# STM32.net
KiCad netlist of a schematic drawn in Altium Designer
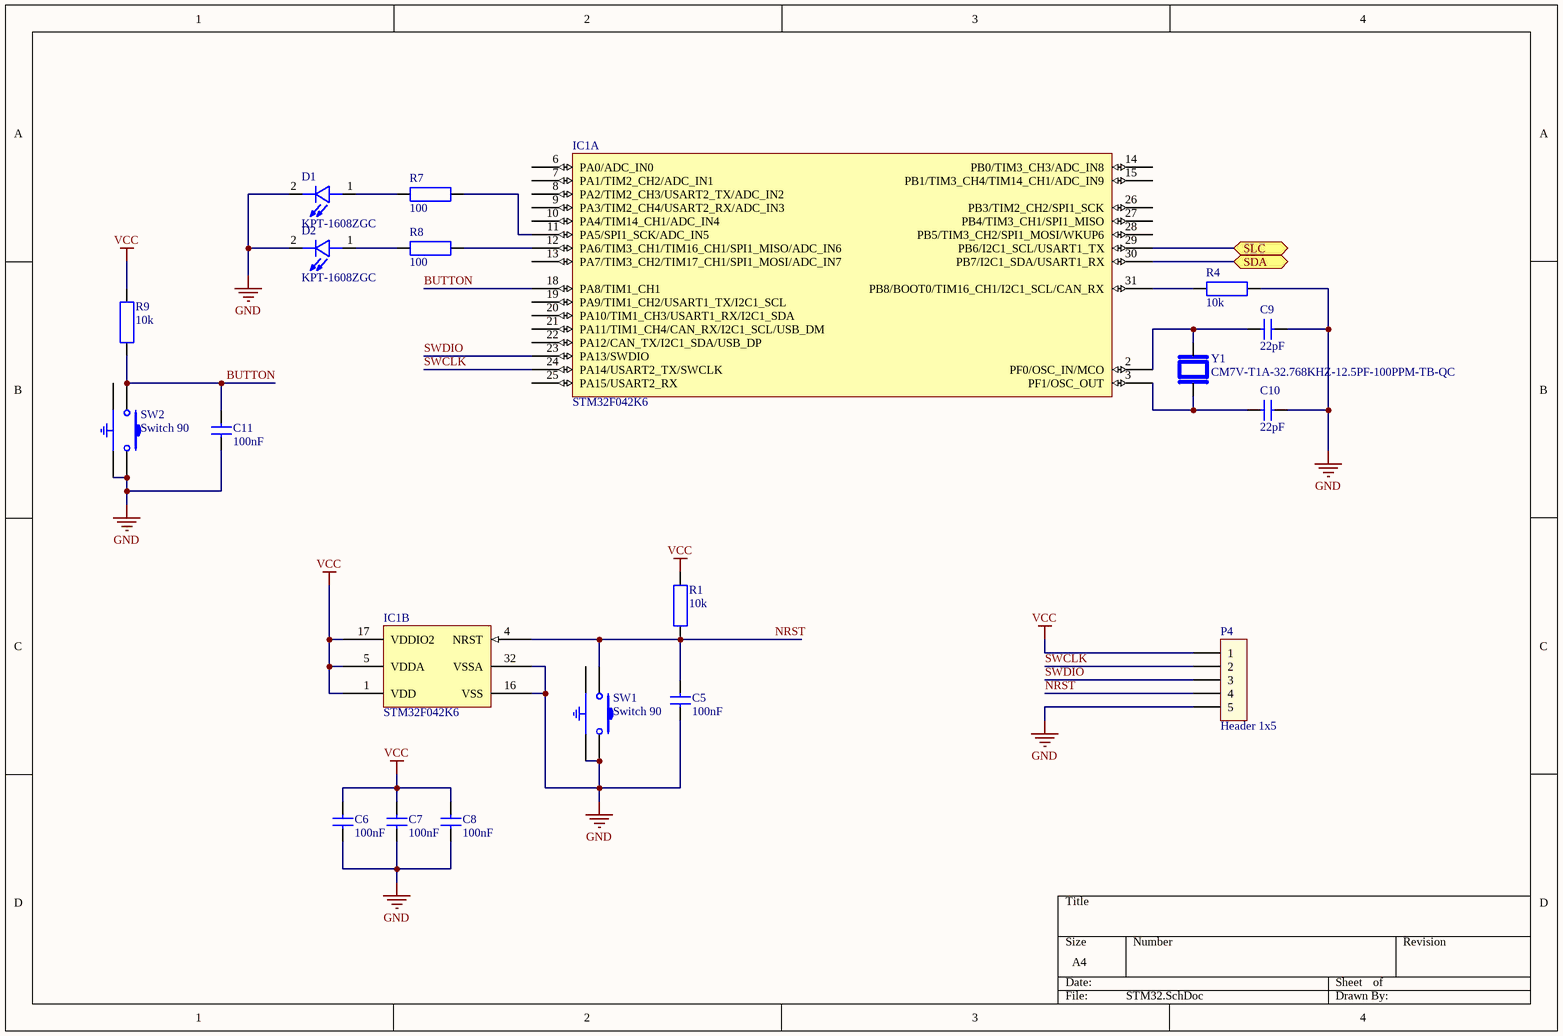
[diagram p0: STM32.SchDoc]

(export (version "E")
  (design (tool "Eeschema 10.0.6"))
  (components
    (comp (ref "C5")
      (value "100nF")
      (footprint "SMD_CAPACITOR_1206")
      (description "Capacitor")
      (libsource (lib "VPP_Library") (part "Capacitor"))
    )
    (comp (ref "C6")
      (value "100nF")
      (footprint "SMD_CAPACITOR_1206")
      (description "Capacitor")
      (libsource (lib "VPP_Library") (part "Capacitor"))
    )
    (comp (ref "C7")
      (value "100nF")
      (footprint "SMD_CAPACITOR_1206")
      (description "Capacitor")
      (libsource (lib "VPP_Library") (part "Capacitor"))
    )
    (comp (ref "C8")
      (value "100nF")
      (footprint "SMD_CAPACITOR_1206")
      (description "Capacitor")
      (libsource (lib "VPP_Library") (part "Capacitor"))
    )
    (comp (ref "C9")
      (value "22pF")
      (footprint "SMD_CAPACITOR_1206")
      (description "Capacitor")
      (libsource (lib "VPP_Library") (part "Capacitor"))
    )
    (comp (ref "C10")
      (value "22pF")
      (footprint "SMD_CAPACITOR_1206")
      (description "Capacitor")
      (libsource (lib "VPP_Library") (part "Capacitor"))
    )
    (comp (ref "C11")
      (value "100nF")
      (footprint "SMD_CAPACITOR_1206")
      (description "Capacitor")
      (libsource (lib "VPP_Library") (part "Capacitor"))
    )
    (comp (ref "D1")
      (value "KPT-1608ZGC")
      (footprint "LED_KPT-1608ZGC")
      (description "1.6x0.8mm Smd Chip Led Lamp")
      (fields (field (name "MF") "Kingbright"))
      (libsource (lib "KPT-1608ZGC") (part "KPT-1608ZGC"))
    )
    (comp (ref "D2")
      (value "KPT-1608ZGC")
      (footprint "LED_KPT-1608ZGC")
      (description "1.6x0.8mm Smd Chip Led Lamp")
      (fields (field (name "MF") "Kingbright"))
      (libsource (lib "KPT-1608ZGC") (part "KPT-1608ZGC"))
    )
    (comp (ref "IC1")
      (value "STM32F042K6")
      (footprint "SMD_LQFP-32")
      (description "ARM Cortex-M0 32-bit MCU, 6 KB Internal RAM, 32 KB Flash, 48 MHz, 32-pin LQFP")
      (libsource (lib "VPP_Library") (part "STM32F042K6"))
    )
    (comp (ref "P4")
      (value "Header 1x5")
      (footprint "THT_HEADER_100MIL_1X5_MALE_90")
      (libsource (lib "VPP_Library") (part "Header_1x5"))
    )
    (comp (ref "R1")
      (value "10k")
      (footprint "SMD_RESISTOR_1206")
      (description "Resistor")
      (libsource (lib "VPP_Library") (part "Resistor"))
    )
    (comp (ref "R4")
      (value "10k")
      (footprint "SMD_RESISTOR_1206")
      (description "Resistor")
      (libsource (lib "VPP_Library") (part "Resistor"))
    )
    (comp (ref "R7")
      (value "100")
      (footprint "SMD_RESISTOR_1206")
      (description "Resistor")
      (libsource (lib "VPP_Library") (part "Resistor"))
    )
    (comp (ref "R8")
      (value "100")
      (footprint "SMD_RESISTOR_1206")
      (description "Resistor")
      (libsource (lib "VPP_Library") (part "Resistor"))
    )
    (comp (ref "R9")
      (value "10k")
      (footprint "SMD_RESISTOR_1206")
      (description "Resistor")
      (libsource (lib "VPP_Library") (part "Resistor"))
    )
    (comp (ref "SW1")
      (value "Switch 90")
      (footprint "SMD_SWITCH_SPST_90")
      (description "Tactile Switch Right Angle")
      (libsource (lib "VPP_Library") (part "Switch_90"))
    )
    (comp (ref "SW2")
      (value "Switch 90")
      (footprint "SMD_SWITCH_SPST_90")
      (description "Tactile Switch Right Angle")
      (libsource (lib "VPP_Library") (part "Switch_90"))
    )
    (comp (ref "Y1")
      (value "CM7V-T1A-32.768KHZ-12.5PF-100PPM-TB-QC")
      (footprint "XTAL_CM7V-T1A-32.768KHZ-12.5PF-100PPM-TB-QC")
      (description "LOW FREQUENCY CRYSTAL")
      (fields
        (field (name "MP") "CM7V-T1A-32.768kHz-12.5pF-100PPM-TB-QC")
        (field (name "MF") "Micro Crystal")
      )
      (libsource (lib "CM7V-T1A-32.768KHZ-12.5PF-100PPM-TB-QC") (part "CM7V-T1A-32.768KHZ-12.5PF-100PPM-TB-QC"))
    )
  )
  (nets
    (net (code "1") (name "/BUTTON") (class "Default")
      (node (ref "C11") (pin "1") (pinfunction "1_1") (pintype "passive"))
      (node (ref "IC1") (pin "18") (pinfunction "PA8/TIM1_CH1_18") (pintype "bidirectional"))
      (node (ref "R9") (pin "2") (pinfunction "2_2") (pintype "passive"))
      (node (ref "SW2") (pin "1") (pinfunction "1_1") (pintype "passive"))
    )
    (net (code "2") (name "/NRST") (class "Default")
      (node (ref "C5") (pin "1") (pinfunction "1_1") (pintype "passive"))
      (node (ref "IC1") (pin "4") (pinfunction "NRST_4") (pintype "input"))
      (node (ref "P4") (pin "4") (pinfunction "4_4") (pintype "passive"))
      (node (ref "R1") (pin "2") (pinfunction "2_2") (pintype "passive"))
      (node (ref "SW1") (pin "1") (pinfunction "1_1") (pintype "passive"))
    )
    (net (code "3") (name "/SDA") (class "Default")
      (node (ref "IC1") (pin "30") (pinfunction "PB7/I2C1_SDA/USART1_RX_30") (pintype "bidirectional"))
    )
    (net (code "4") (name "/SLC") (class "Default")
      (node (ref "IC1") (pin "29") (pinfunction "PB6/I2C1_SCL/USART1_TX_29") (pintype "bidirectional"))
    )
    (net (code "5") (name "/SWCLK") (class "Default")
      (node (ref "IC1") (pin "24") (pinfunction "PA14/USART2_TX/SWCLK_24") (pintype "bidirectional"))
      (node (ref "P4") (pin "2") (pinfunction "2_2") (pintype "passive"))
    )
    (net (code "6") (name "/SWDIO") (class "Default")
      (node (ref "IC1") (pin "23") (pinfunction "PA13/SWDIO_23") (pintype "bidirectional"))
      (node (ref "P4") (pin "3") (pinfunction "3_3") (pintype "passive"))
    )
    (net (code "7") (name "GND") (class "Default")
      (node (ref "C10") (pin "2") (pinfunction "2_2") (pintype "passive"))
      (node (ref "C11") (pin "2") (pinfunction "2_2") (pintype "passive"))
      (node (ref "C5") (pin "2") (pinfunction "2_2") (pintype "passive"))
      (node (ref "C6") (pin "1") (pinfunction "1_1") (pintype "passive"))
      (node (ref "C7") (pin "1") (pinfunction "1_1") (pintype "passive"))
      (node (ref "C8") (pin "2") (pinfunction "2_2") (pintype "passive"))
      (node (ref "C9") (pin "2") (pinfunction "2_2") (pintype "passive"))
      (node (ref "D1") (pin "2") (pinfunction "C_2") (pintype "passive"))
      (node (ref "D2") (pin "2") (pinfunction "C_2") (pintype "passive"))
      (node (ref "IC1") (pin "16") (pinfunction "VSS_16") (pintype "power_in"))
      (node (ref "IC1") (pin "32") (pinfunction "VSSA_32") (pintype "power_in"))
      (node (ref "P4") (pin "5") (pinfunction "5_5") (pintype "passive"))
      (node (ref "R4") (pin "2") (pinfunction "2_2") (pintype "passive"))
      (node (ref "SW1") (pin "2") (pinfunction "2_2") (pintype "passive"))
      (node (ref "SW1") (pin "4") (pinfunction "4_4") (pintype "passive"))
      (node (ref "SW2") (pin "2") (pinfunction "2_2") (pintype "passive"))
      (node (ref "SW2") (pin "4") (pinfunction "4_4") (pintype "passive"))
    )
    (net (code "8") (name "Net-(D1-A)") (class "Default")
      (node (ref "D1") (pin "1") (pinfunction "A_1") (pintype "passive"))
      (node (ref "R7") (pin "1") (pinfunction "1_1") (pintype "passive"))
    )
    (net (code "9") (name "Net-(D2-A)") (class "Default")
      (node (ref "D2") (pin "1") (pinfunction "A_1") (pintype "passive"))
      (node (ref "R8") (pin "1") (pinfunction "1_1") (pintype "passive"))
    )
    (net (code "10") (name "Net-(IC1A-PA5{slash}SPI1_SCK{slash}ADC_IN5)") (class "Default")
      (node (ref "IC1") (pin "11") (pinfunction "PA5/SPI1_SCK/ADC_IN5_11") (pintype "bidirectional"))
      (node (ref "R7") (pin "2") (pinfunction "2_2") (pintype "passive"))
    )
    (net (code "11") (name "Net-(IC1A-PA6{slash}TIM3_CH1{slash}TIM16_CH1{slash}SPI1_MISO{slash}ADC_IN6)") (class "Default")
      (node (ref "IC1") (pin "12") (pinfunction "PA6/TIM3_CH1/TIM16_CH1/SPI1_MISO/ADC_IN6_12") (pintype "bidirectional"))
      (node (ref "R8") (pin "2") (pinfunction "2_2") (pintype "passive"))
    )
    (net (code "12") (name "Net-(IC1A-PB8{slash}BOOT0{slash}TIM16_CH1{slash}I2C1_SCL{slash}CAN_RX)") (class "Default")
      (node (ref "IC1") (pin "31") (pinfunction "PB8/BOOT0/TIM16_CH1/I2C1_SCL/CAN_RX_31") (pintype "bidirectional"))
      (node (ref "R4") (pin "1") (pinfunction "1_1") (pintype "passive"))
    )
    (net (code "13") (name "Net-(IC1A-PF0{slash}OSC_IN{slash}MCO)") (class "Default")
      (node (ref "C9") (pin "1") (pinfunction "1_1") (pintype "passive"))
      (node (ref "IC1") (pin "2") (pinfunction "PF0/OSC_IN/MCO_2") (pintype "bidirectional"))
      (node (ref "Y1") (pin "1") (pinfunction "1_1") (pintype "passive"))
    )
    (net (code "14") (name "Net-(IC1A-PF1{slash}OSC_OUT)") (class "Default")
      (node (ref "C10") (pin "1") (pinfunction "1_1") (pintype "passive"))
      (node (ref "IC1") (pin "3") (pinfunction "PF1/OSC_OUT_3") (pintype "bidirectional"))
      (node (ref "Y1") (pin "2") (pinfunction "2_2") (pintype "passive"))
    )
    (net (code "15") (name "VCC") (class "Default")
      (node (ref "C6") (pin "2") (pinfunction "2_2") (pintype "passive"))
      (node (ref "C7") (pin "2") (pinfunction "2_2") (pintype "passive"))
      (node (ref "C8") (pin "1") (pinfunction "1_1") (pintype "passive"))
      (node (ref "IC1") (pin "1") (pinfunction "VDD_1") (pintype "power_in"))
      (node (ref "IC1") (pin "17") (pinfunction "VDDIO2_17") (pintype "power_in"))
      (node (ref "IC1") (pin "5") (pinfunction "VDDA_5") (pintype "power_in"))
      (node (ref "P4") (pin "1") (pinfunction "1_1") (pintype "passive"))
      (node (ref "R1") (pin "1") (pinfunction "1_1") (pintype "passive"))
      (node (ref "R9") (pin "1") (pinfunction "1_1") (pintype "passive"))
    )
    (net (code "16") (name "unconnected-(IC1A-PA0{slash}ADC_IN0-Pad6)") (class "Default")
      (node (ref "IC1") (pin "6") (pinfunction "PA0/ADC_IN0_6") (pintype "bidirectional"))
    )
    (net (code "17") (name "unconnected-(IC1A-PA1{slash}TIM2_CH2{slash}ADC_IN1-Pad7)") (class "Default")
      (node (ref "IC1") (pin "7") (pinfunction "PA1/TIM2_CH2/ADC_IN1_7") (pintype "bidirectional"))
    )
    (net (code "18") (name "unconnected-(IC1A-PA2{slash}TIM2_CH3{slash}USART2_TX{slash}ADC_IN2-Pad8)") (class "Default")
      (node (ref "IC1") (pin "8") (pinfunction "PA2/TIM2_CH3/USART2_TX/ADC_IN2_8") (pintype "bidirectional"))
    )
    (net (code "19") (name "unconnected-(IC1A-PA3{slash}TIM2_CH4{slash}USART2_RX{slash}ADC_IN3-Pad9)") (class "Default")
      (node (ref "IC1") (pin "9") (pinfunction "PA3/TIM2_CH4/USART2_RX/ADC_IN3_9") (pintype "bidirectional"))
    )
    (net (code "20") (name "unconnected-(IC1A-PA4{slash}TIM14_CH1{slash}ADC_IN4-Pad10)") (class "Default")
      (node (ref "IC1") (pin "10") (pinfunction "PA4/TIM14_CH1/ADC_IN4_10") (pintype "bidirectional"))
    )
    (net (code "21") (name "unconnected-(IC1A-PA7{slash}TIM3_CH2{slash}TIM17_CH1{slash}SPI1_MOSI{slash}ADC_IN7-Pad13)") (class "Default")
      (node (ref "IC1") (pin "13") (pinfunction "PA7/TIM3_CH2/TIM17_CH1/SPI1_MOSI/ADC_IN7_13") (pintype "bidirectional"))
    )
    (net (code "22") (name "unconnected-(IC1A-PA9{slash}TIM1_CH2{slash}USART1_TX{slash}I2C1_SCL-Pad19)") (class "Default")
      (node (ref "IC1") (pin "19") (pinfunction "PA9/TIM1_CH2/USART1_TX/I2C1_SCL_19") (pintype "bidirectional"))
    )
    (net (code "23") (name "unconnected-(IC1A-PA10{slash}TIM1_CH3{slash}USART1_RX{slash}I2C1_SDA-Pad20)") (class "Default")
      (node (ref "IC1") (pin "20") (pinfunction "PA10/TIM1_CH3/USART1_RX/I2C1_SDA_20") (pintype "bidirectional"))
    )
    (net (code "24") (name "unconnected-(IC1A-PA11{slash}TIM1_CH4{slash}CAN_RX{slash}I2C1_SCL{slash}USB_DM-Pad21)") (class "Default")
      (node (ref "IC1") (pin "21") (pinfunction "PA11/TIM1_CH4/CAN_RX/I2C1_SCL/USB_DM_21") (pintype "bidirectional"))
    )
    (net (code "25") (name "unconnected-(IC1A-PA12{slash}CAN_TX{slash}I2C1_SDA{slash}USB_DP-Pad22)") (class "Default")
      (node (ref "IC1") (pin "22") (pinfunction "PA12/CAN_TX/I2C1_SDA/USB_DP_22") (pintype "bidirectional"))
    )
    (net (code "26") (name "unconnected-(IC1A-PA15{slash}USART2_RX-Pad25)") (class "Default")
      (node (ref "IC1") (pin "25") (pinfunction "PA15/USART2_RX_25") (pintype "bidirectional"))
    )
    (net (code "27") (name "unconnected-(IC1A-PB0{slash}TIM3_CH3{slash}ADC_IN8-Pad14)") (class "Default")
      (node (ref "IC1") (pin "14") (pinfunction "PB0/TIM3_CH3/ADC_IN8_14") (pintype "bidirectional"))
    )
    (net (code "28") (name "unconnected-(IC1A-PB1{slash}TIM3_CH4{slash}TIM14_CH1{slash}ADC_IN9-Pad15)") (class "Default")
      (node (ref "IC1") (pin "15") (pinfunction "PB1/TIM3_CH4/TIM14_CH1/ADC_IN9_15") (pintype "bidirectional"))
    )
    (net (code "29") (name "unconnected-(IC1A-PB3{slash}TIM2_CH2{slash}SPI1_SCK-Pad26)") (class "Default")
      (node (ref "IC1") (pin "26") (pinfunction "PB3/TIM2_CH2/SPI1_SCK_26") (pintype "bidirectional"))
    )
    (net (code "30") (name "unconnected-(IC1A-PB4{slash}TIM3_CH1{slash}SPI1_MISO-Pad27)") (class "Default")
      (node (ref "IC1") (pin "27") (pinfunction "PB4/TIM3_CH1/SPI1_MISO_27") (pintype "bidirectional"))
    )
    (net (code "31") (name "unconnected-(IC1A-PB5{slash}TIM3_CH2{slash}SPI1_MOSI{slash}WKUP6-Pad28)") (class "Default")
      (node (ref "IC1") (pin "28") (pinfunction "PB5/TIM3_CH2/SPI1_MOSI/WKUP6_28") (pintype "bidirectional"))
    )
    (net (code "32") (name "unconnected-(SW1-Pad3)") (class "Default")
      (node (ref "SW1") (pin "3") (pinfunction "3_3") (pintype "passive"))
    )
    (net (code "33") (name "unconnected-(SW2-Pad3)") (class "Default")
      (node (ref "SW2") (pin "3") (pinfunction "3_3") (pintype "passive"))
    )
  )
)
